# mixer_30mil_1GHz.net
KiCad netlist of a schematic drawn in Altium Designer
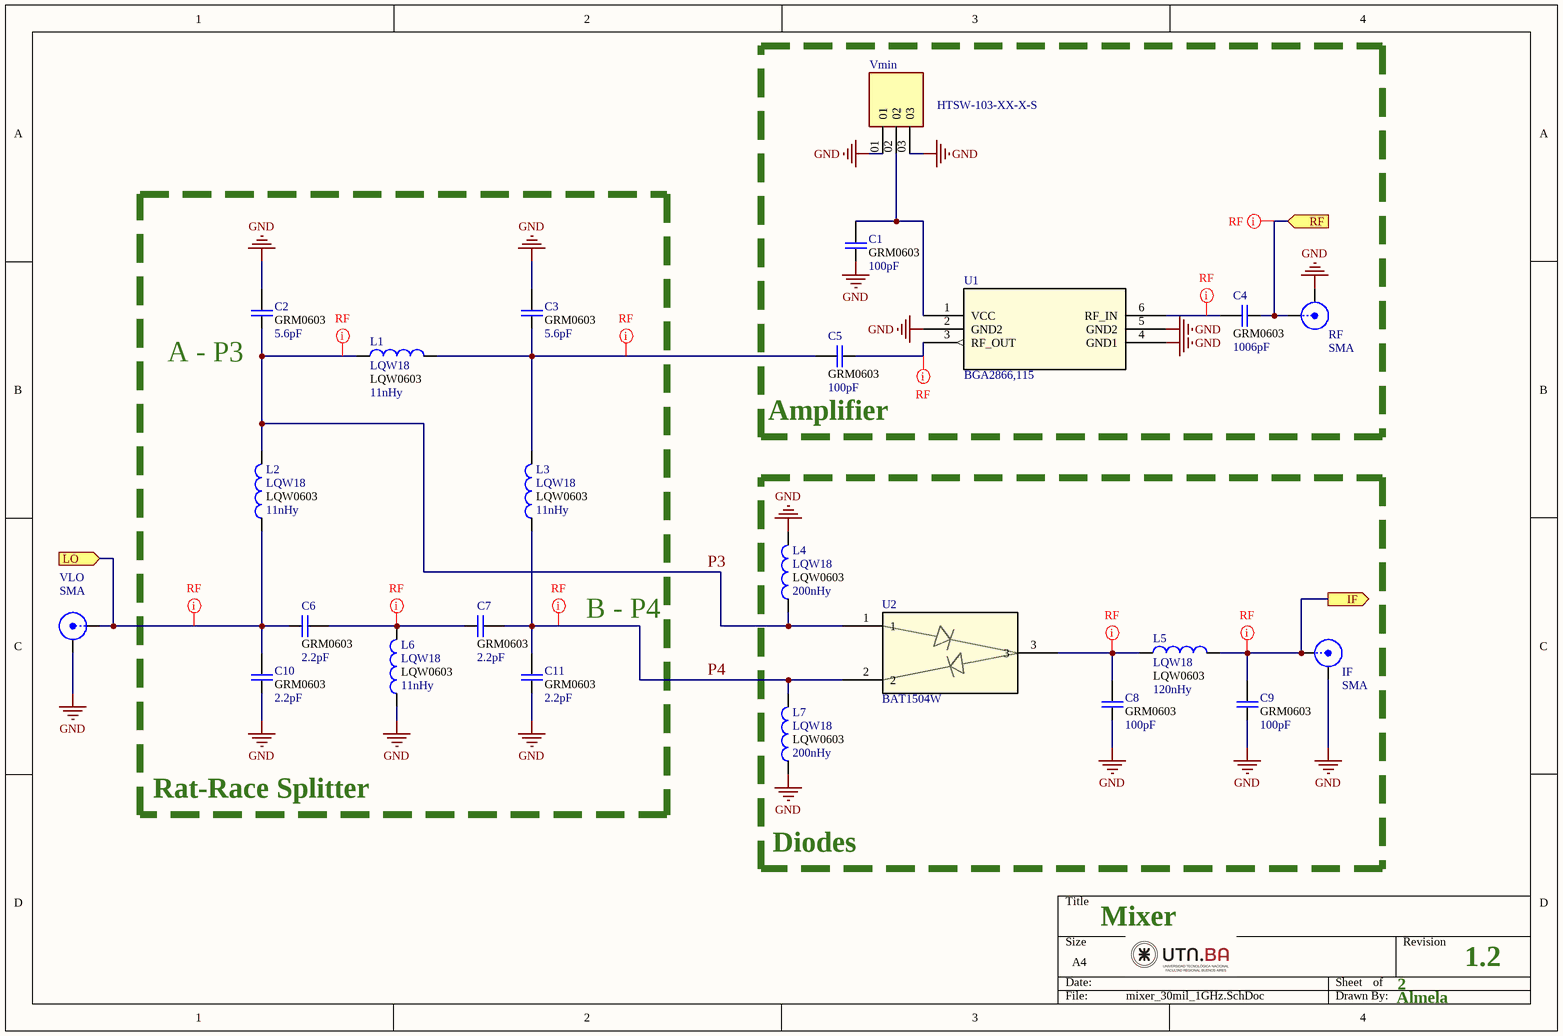
[diagram p0: mixer_30mil_1GHz.SchDoc]

(export (version "E")
  (design (tool "Eeschema 10.0.6"))
  (components
    (comp (ref "C1")
      (value "100pF")
      (footprint "GRM0603")
      (description "Capacitor GRM18 0603")
      (fields (field (name "Comment") "Cap 0603") (field (name "PUBLISHER") "Altium Limited"))
      (libsource (lib "Radar_RF_EAIII") (part "Cap"))
    )
    (comp (ref "C2")
      (value "5.6pF")
      (footprint "GRM0603")
      (description "Capacitor GRM18 0603")
      (fields (field (name "Comment") "Cap 0603") (field (name "PUBLISHER") "Altium Limited"))
      (libsource (lib "Radar_RF_EAIII") (part "Cap"))
    )
    (comp (ref "C3")
      (value "5.6pF")
      (footprint "GRM0603")
      (description "Capacitor GRM18 0603")
      (fields (field (name "Comment") "Cap 0603") (field (name "PUBLISHER") "Altium Limited"))
      (libsource (lib "Radar_RF_EAIII") (part "Cap"))
    )
    (comp (ref "C4")
      (value "1006pF")
      (footprint "GRM0603")
      (description "Capacitor GRM18 0603")
      (fields (field (name "Comment") "Cap 0603") (field (name "PUBLISHER") "Altium Limited"))
      (libsource (lib "Radar_RF_EAIII") (part "Cap"))
    )
    (comp (ref "C5")
      (value "100pF")
      (footprint "GRM0603")
      (description "Capacitor GRM18 0603")
      (fields (field (name "Comment") "Cap 0603") (field (name "PUBLISHER") "Altium Limited"))
      (libsource (lib "Radar_RF_EAIII") (part "Cap"))
    )
    (comp (ref "C6")
      (value "2.2pF")
      (footprint "GRM0603")
      (description "Capacitor GRM18 0603")
      (fields (field (name "Comment") "Cap 0603") (field (name "PUBLISHER") "Altium Limited"))
      (libsource (lib "Radar_RF_EAIII") (part "Cap"))
    )
    (comp (ref "C7")
      (value "2.2pF")
      (footprint "GRM0603")
      (description "Capacitor GRM18 0603")
      (fields (field (name "Comment") "Cap 0603") (field (name "PUBLISHER") "Altium Limited"))
      (libsource (lib "Radar_RF_EAIII") (part "Cap"))
    )
    (comp (ref "C8")
      (value "100pF")
      (footprint "GRM0603")
      (description "Capacitor GRM18 0603")
      (fields (field (name "Comment") "Cap 0603") (field (name "PUBLISHER") "Altium Limited"))
      (libsource (lib "Radar_RF_EAIII") (part "Cap"))
    )
    (comp (ref "C9")
      (value "100pF")
      (footprint "GRM0603")
      (description "Capacitor GRM18 0603")
      (fields (field (name "Comment") "Cap 0603") (field (name "PUBLISHER") "Altium Limited"))
      (libsource (lib "Radar_RF_EAIII") (part "Cap"))
    )
    (comp (ref "C10")
      (value "2.2pF")
      (footprint "GRM0603")
      (description "Capacitor GRM18 0603")
      (fields (field (name "Comment") "Cap 0603") (field (name "PUBLISHER") "Altium Limited"))
      (libsource (lib "Radar_RF_EAIII") (part "Cap"))
    )
    (comp (ref "C11")
      (value "2.2pF")
      (footprint "GRM0603")
      (description "Capacitor GRM18 0603")
      (fields (field (name "Comment") "Cap 0603") (field (name "PUBLISHER") "Altium Limited"))
      (libsource (lib "Radar_RF_EAIII") (part "Cap"))
    )
    (comp (ref "IF")
      (value "SMA")
      (footprint "SMA-142-0701-851")
      (description "SMB Straight Connector")
      (fields (field (name "PUBLISHER") "Altium Limited"))
      (libsource (lib "PCB_Project") (part "SMB"))
    )
    (comp (ref "L1")
      (value "LQW18")
      (footprint "INDC1608X100N")
      (description "Ind RF Chip Wirewound 18nH 5% 100MHz 40Q-Factor 550mA 0603 Paper T/R")
      (fields
        (field (name "MP") "LQW18AN18NJ00D")
        (field (name "PARAMETER 1") "LQW0603")
        (field (name "ALTIUM_VALUE") "11nHy")
      )
      (libsource (lib "Radar_RF_EAIII") (part "LQW18"))
    )
    (comp (ref "L2")
      (value "LQW18")
      (footprint "INDC1608X100N")
      (description "Ind RF Chip Wirewound 18nH 5% 100MHz 40Q-Factor 550mA 0603 Paper T/R")
      (fields
        (field (name "MP") "LQW18AN18NJ00D")
        (field (name "PARAMETER 1") "LQW0603")
        (field (name "ALTIUM_VALUE") "11nHy")
      )
      (libsource (lib "Radar_RF_EAIII") (part "LQW18"))
    )
    (comp (ref "L3")
      (value "LQW18")
      (footprint "INDC1608X100N")
      (description "Ind RF Chip Wirewound 18nH 5% 100MHz 40Q-Factor 550mA 0603 Paper T/R")
      (fields
        (field (name "MP") "LQW18AN18NJ00D")
        (field (name "PARAMETER 1") "LQW0603")
        (field (name "ALTIUM_VALUE") "11nHy")
      )
      (libsource (lib "Radar_RF_EAIII") (part "LQW18"))
    )
    (comp (ref "L4")
      (value "LQW18")
      (footprint "INDC1608X100N")
      (description "Ind RF Chip Wirewound 18nH 5% 100MHz 40Q-Factor 550mA 0603 Paper T/R")
      (fields
        (field (name "MP") "LQW18AN18NJ00D")
        (field (name "PARAMETER 1") "LQW0603")
        (field (name "ALTIUM_VALUE") "200nHy")
      )
      (libsource (lib "Radar_RF_EAIII") (part "LQW18"))
    )
    (comp (ref "L5")
      (value "LQW18")
      (footprint "INDC1608X100N")
      (description "Ind RF Chip Wirewound 18nH 5% 100MHz 40Q-Factor 550mA 0603 Paper T/R")
      (fields
        (field (name "MP") "LQW18AN18NJ00D")
        (field (name "PARAMETER 1") "LQW0603")
        (field (name "ALTIUM_VALUE") "120nHy")
      )
      (libsource (lib "Radar_RF_EAIII") (part "LQW18"))
    )
    (comp (ref "L6")
      (value "LQW18")
      (footprint "INDC1608X100N")
      (description "Ind RF Chip Wirewound 18nH 5% 100MHz 40Q-Factor 550mA 0603 Paper T/R")
      (fields
        (field (name "MP") "LQW18AN18NJ00D")
        (field (name "PARAMETER 1") "LQW0603")
        (field (name "ALTIUM_VALUE") "11nHy")
      )
      (libsource (lib "Radar_RF_EAIII") (part "LQW18"))
    )
    (comp (ref "L7")
      (value "LQW18")
      (footprint "INDC1608X100N")
      (description "Ind RF Chip Wirewound 18nH 5% 100MHz 40Q-Factor 550mA 0603 Paper T/R")
      (fields
        (field (name "MP") "LQW18AN18NJ00D")
        (field (name "PARAMETER 1") "LQW0603")
        (field (name "ALTIUM_VALUE") "200nHy")
      )
      (libsource (lib "Radar_RF_EAIII") (part "LQW18"))
    )
    (comp (ref "RF")
      (value "SMA")
      (footprint "SMA-142-0701-851")
      (description "SMB Straight Connector")
      (fields (field (name "PUBLISHER") "Altium Limited"))
      (libsource (lib "PCB_Project") (part "SMB"))
    )
    (comp (ref "U1")
      (value "BGA2866,115")
      (footprint "SOT363_NXP")
      (description "No Description Available")
      (libsource (lib "Radar_RF_EAIII") (part "BGA2866,115"))
    )
    (comp (ref "U2")
      (value "BAT1504W")
      (footprint "SOT_327XTSA1_INF")
      (description "Diodo")
      (libsource (lib "Radar_RF_EAIII") (part "BAT1504W"))
    )
    (comp (ref "VLO")
      (value "SMA")
      (footprint "SMA-142-0701-851")
      (description "SMB Straight Connector")
      (fields (field (name "PUBLISHER") "Altium Limited"))
      (libsource (lib "PCB_Project") (part "SMB"))
    )
    (comp (ref "Vmin")
      (value "HTSW-103-XX-X-S")
      (footprint "SAMTEC_HTSW-103-XX-X-S")
      (description "Conn Unshrouded Header HDR 3 POS 2.54mm Solder ST Top Entry Thru-Hole Bag")
      (fields (field (name "MP") "HTSW-103-08-S-S") (field (name "MF") "Samtec"))
      (libsource (lib "HTSW-103-XX-X-S") (part "HTSW-103-XX-X-S"))
    )
  )
  (nets
    (net (code "1") (name "/IF") (class "Default")
      (node (ref "C9") (pin "2") (pinfunction "2_2") (pintype "passive"))
      (node (ref "IF") (pin "1") (pinfunction "X_1") (pintype "passive"))
      (node (ref "L5") (pin "2") (pinfunction "2_2") (pintype "passive"))
    )
    (net (code "2") (name "/LO") (class "Default")
      (node (ref "C10") (pin "2") (pinfunction "2_2") (pintype "passive"))
      (node (ref "C6") (pin "1") (pinfunction "1_1") (pintype "passive"))
      (node (ref "L2") (pin "1") (pinfunction "1_1") (pintype "passive"))
      (node (ref "VLO") (pin "1") (pinfunction "X_1") (pintype "passive"))
    )
    (net (code "3") (name "/P3") (class "Default")
      (node (ref "C2") (pin "1") (pinfunction "1_1") (pintype "passive"))
      (node (ref "L1") (pin "1") (pinfunction "1_1") (pintype "passive"))
      (node (ref "L2") (pin "2") (pinfunction "2_2") (pintype "passive"))
      (node (ref "L4") (pin "1") (pinfunction "1_1") (pintype "passive"))
      (node (ref "U2") (pin "1") (pinfunction "1_1") (pintype "passive"))
    )
    (net (code "4") (name "/P4") (class "Default")
      (node (ref "C11") (pin "2") (pinfunction "2_2") (pintype "passive"))
      (node (ref "C7") (pin "2") (pinfunction "2_2") (pintype "passive"))
      (node (ref "L3") (pin "1") (pinfunction "1_1") (pintype "passive"))
      (node (ref "L7") (pin "2") (pinfunction "2_2") (pintype "passive"))
      (node (ref "U2") (pin "2") (pinfunction "2_2") (pintype "passive"))
    )
    (net (code "5") (name "/RF") (class "Default")
      (node (ref "C4") (pin "1") (pinfunction "1_1") (pintype "passive"))
      (node (ref "RF") (pin "1") (pinfunction "X_1") (pintype "passive"))
    )
    (net (code "6") (name "GND") (class "Default")
      (node (ref "C1") (pin "1") (pinfunction "1_1") (pintype "passive"))
      (node (ref "C10") (pin "1") (pinfunction "1_1") (pintype "passive"))
      (node (ref "C11") (pin "1") (pinfunction "1_1") (pintype "passive"))
      (node (ref "C2") (pin "2") (pinfunction "2_2") (pintype "passive"))
      (node (ref "C3") (pin "2") (pinfunction "2_2") (pintype "passive"))
      (node (ref "C8") (pin "1") (pinfunction "1_1") (pintype "passive"))
      (node (ref "C9") (pin "1") (pinfunction "1_1") (pintype "passive"))
      (node (ref "IF") (pin "2") (pinfunction "Y_2") (pintype "passive"))
      (node (ref "L4") (pin "2") (pinfunction "2_2") (pintype "passive"))
      (node (ref "L6") (pin "1") (pinfunction "1_1") (pintype "passive"))
      (node (ref "L7") (pin "1") (pinfunction "1_1") (pintype "passive"))
      (node (ref "RF") (pin "2") (pinfunction "Y_2") (pintype "passive"))
      (node (ref "U1") (pin "2") (pinfunction "GND2_2") (pintype "power_in"))
      (node (ref "U1") (pin "4") (pinfunction "GND1_4") (pintype "power_in"))
      (node (ref "U1") (pin "5") (pinfunction "GND2_5") (pintype "power_in"))
      (node (ref "VLO") (pin "2") (pinfunction "Y_2") (pintype "passive"))
      (node (ref "Vmin") (pin "01") (pinfunction "01_01") (pintype "passive"))
      (node (ref "Vmin") (pin "03") (pinfunction "03_03") (pintype "passive"))
    )
    (net (code "7") (name "Net-(C3-Pad1)") (class "Default")
      (node (ref "C3") (pin "1") (pinfunction "1_1") (pintype "passive"))
      (node (ref "C5") (pin "2") (pinfunction "2_2") (pintype "passive"))
      (node (ref "L1") (pin "2") (pinfunction "2_2") (pintype "passive"))
      (node (ref "L3") (pin "2") (pinfunction "2_2") (pintype "passive"))
    )
    (net (code "8") (name "Net-(C6-Pad2)") (class "Default")
      (node (ref "C6") (pin "2") (pinfunction "2_2") (pintype "passive"))
      (node (ref "C7") (pin "1") (pinfunction "1_1") (pintype "passive"))
      (node (ref "L6") (pin "2") (pinfunction "2_2") (pintype "passive"))
    )
    (net (code "9") (name "Net-(C8-Pad2)") (class "Default")
      (node (ref "C8") (pin "2") (pinfunction "2_2") (pintype "passive"))
      (node (ref "L5") (pin "1") (pinfunction "1_1") (pintype "passive"))
      (node (ref "U2") (pin "3") (pinfunction "3_3") (pintype "passive"))
    )
    (net (code "10") (name "Net-(U1-RF_IN)") (class "Default")
      (node (ref "C4") (pin "2") (pinfunction "2_2") (pintype "passive"))
      (node (ref "U1") (pin "6") (pinfunction "RF_IN_6") (pintype "passive"))
    )
    (net (code "11") (name "Net-(U1-RF_OUT)") (class "Default")
      (node (ref "C5") (pin "1") (pinfunction "1_1") (pintype "passive"))
      (node (ref "U1") (pin "3") (pinfunction "RF_OUT_3") (pintype "output"))
    )
    (net (code "12") (name "Net-(U1-VCC)") (class "Default")
      (node (ref "C1") (pin "2") (pinfunction "2_2") (pintype "passive"))
      (node (ref "U1") (pin "1") (pinfunction "VCC_1") (pintype "power_in"))
      (node (ref "Vmin") (pin "02") (pinfunction "02_02") (pintype "passive"))
    )
  )
)
